# segundo_piso.net
KiCad netlist of a schematic drawn in EAGLE
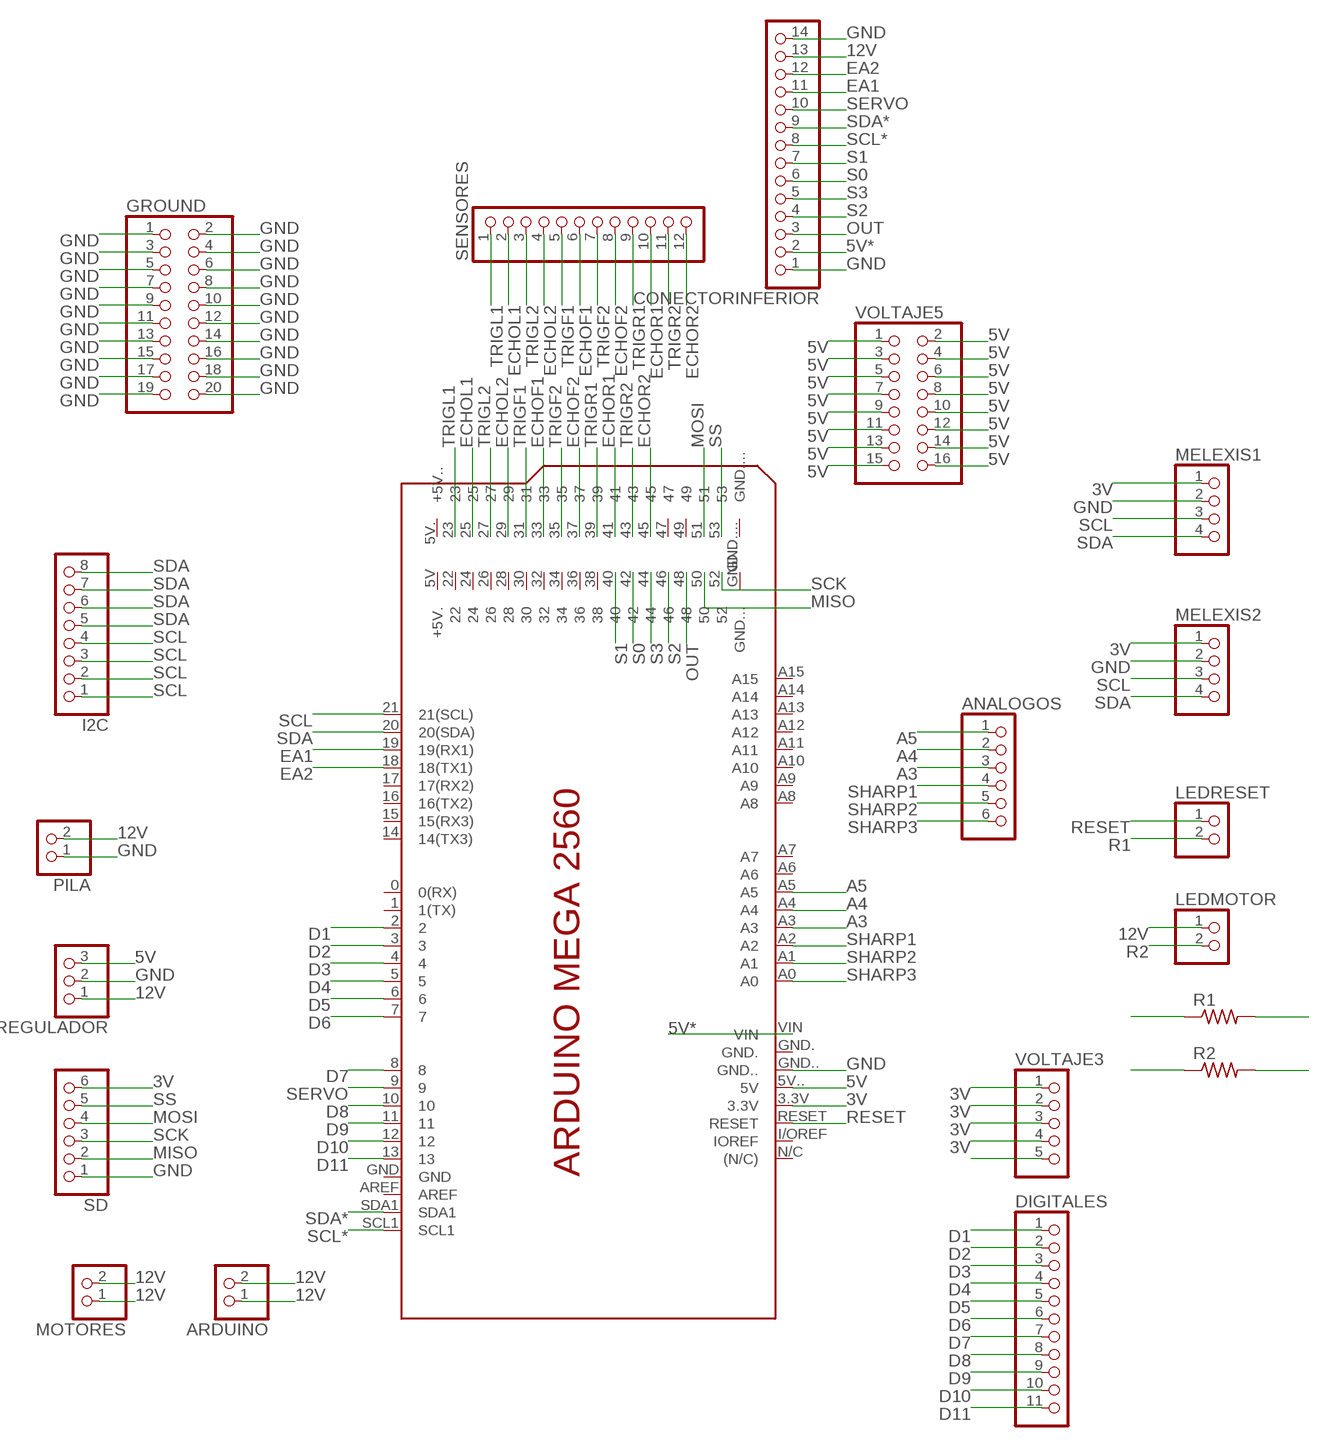
[diagram p0: schematic, sheet 1]

(export (version "E")
  (design (tool "Eeschema 10.0.6"))
  (components
    (comp (ref "ANALOGOS")
      (value "PINHD-1X6")
      (footprint "eagle-import:1X06")
      (libsource (lib "eagle-import") (part "PINHD-1X6"))
    )
    (comp (ref "ARDUINO")
      (value "PINHD-1X2")
      (footprint "eagle-import:1X02")
      (libsource (lib "eagle-import") (part "PINHD-1X2"))
    )
    (comp (ref "CONECTORINFERIOR")
      (value "PINHD-1X14")
      (footprint "eagle-import:1X14")
      (libsource (lib "eagle-import") (part "PINHD-1X14"))
    )
    (comp (ref "DIGITALES")
      (value "PINHD-1X11")
      (footprint "eagle-import:1X11")
      (libsource (lib "eagle-import") (part "PINHD-1X11"))
    )
    (comp (ref "GROUND")
      (value "PINHD-2X10")
      (footprint "eagle-import:2X10")
      (libsource (lib "eagle-import") (part "PINHD-2X10"))
    )
    (comp (ref "I2C")
      (value "PINHD-1X8")
      (footprint "eagle-import:1X08")
      (libsource (lib "eagle-import") (part "PINHD-1X8"))
    )
    (comp (ref "LEDMOTOR")
      (value "PINHD-1X2")
      (footprint "eagle-import:1X02")
      (libsource (lib "eagle-import") (part "PINHD-1X2"))
    )
    (comp (ref "LEDRESET")
      (value "PINHD-1X2")
      (footprint "eagle-import:1X02")
      (libsource (lib "eagle-import") (part "PINHD-1X2"))
    )
    (comp (ref "MEGA1")
      (value "MEGA")
      (footprint "eagle-import:MEGA")
      (libsource (lib "eagle-import") (part "MEGA"))
    )
    (comp (ref "MELEXIS1")
      (value "PINHD-1X4")
      (footprint "eagle-import:1X04")
      (libsource (lib "eagle-import") (part "PINHD-1X4"))
    )
    (comp (ref "MELEXIS2")
      (value "PINHD-1X4")
      (footprint "eagle-import:1X04")
      (libsource (lib "eagle-import") (part "PINHD-1X4"))
    )
    (comp (ref "MOTORES")
      (value "PINHD-1X2")
      (footprint "eagle-import:1X02")
      (libsource (lib "eagle-import") (part "PINHD-1X2"))
    )
    (comp (ref "PILA")
      (value "PINHD-1X2")
      (footprint "eagle-import:1X02")
      (libsource (lib "eagle-import") (part "PINHD-1X2"))
    )
    (comp (ref "R1")
      (value "R-US_0204/7")
      (footprint "eagle-import:0204_7")
      (libsource (lib "eagle-import") (part "R-US_0204/7"))
    )
    (comp (ref "R2")
      (value "R-US_0204/7")
      (footprint "eagle-import:0204_7")
      (libsource (lib "eagle-import") (part "R-US_0204/7"))
    )
    (comp (ref "REGULADOR")
      (value "PINHD-1X3")
      (footprint "eagle-import:1X03")
      (libsource (lib "eagle-import") (part "PINHD-1X3"))
    )
    (comp (ref "SD")
      (value "PINHD-1X6")
      (footprint "eagle-import:1X06")
      (libsource (lib "eagle-import") (part "PINHD-1X6"))
    )
    (comp (ref "SENSORES")
      (value "PINHD-1X12")
      (footprint "eagle-import:1X12")
      (libsource (lib "eagle-import") (part "PINHD-1X12"))
    )
    (comp (ref "VOLTAJE3")
      (value "PINHD-1X5")
      (footprint "eagle-import:1X05")
      (libsource (lib "eagle-import") (part "PINHD-1X5"))
    )
    (comp (ref "VOLTAJE5")
      (value "PINHD-2X8")
      (footprint "eagle-import:2X08")
      (libsource (lib "eagle-import") (part "PINHD-2X8"))
    )
  )
  (nets
    (net (code "1") (name "/3V") (class "Default")
      (node (ref "MEGA1") (pin "3.3V") (pinfunction "3.3V_3.3V") (pintype "bidirectional"))
      (node (ref "MELEXIS1") (pin "1") (pinfunction "1_1") (pintype "passive"))
      (node (ref "MELEXIS2") (pin "1") (pinfunction "1_1") (pintype "passive"))
      (node (ref "SD") (pin "6") (pinfunction "6_6") (pintype "passive"))
      (node (ref "VOLTAJE3") (pin "1") (pinfunction "1_1") (pintype "passive"))
      (node (ref "VOLTAJE3") (pin "2") (pinfunction "2_2") (pintype "passive"))
      (node (ref "VOLTAJE3") (pin "3") (pinfunction "3_3") (pintype "passive"))
      (node (ref "VOLTAJE3") (pin "4") (pinfunction "4_4") (pintype "passive"))
    )
    (net (code "2") (name "/5V") (class "Default")
      (node (ref "MEGA1") (pin "5V..") (pinfunction "5V_5V..") (pintype "bidirectional"))
      (node (ref "REGULADOR") (pin "3") (pinfunction "3_3") (pintype "passive"))
      (node (ref "VOLTAJE5") (pin "1") (pinfunction "1_1") (pintype "passive"))
      (node (ref "VOLTAJE5") (pin "10") (pinfunction "10_10") (pintype "passive"))
      (node (ref "VOLTAJE5") (pin "11") (pinfunction "11_11") (pintype "passive"))
      (node (ref "VOLTAJE5") (pin "12") (pinfunction "12_12") (pintype "passive"))
      (node (ref "VOLTAJE5") (pin "13") (pinfunction "13_13") (pintype "passive"))
      (node (ref "VOLTAJE5") (pin "14") (pinfunction "14_14") (pintype "passive"))
      (node (ref "VOLTAJE5") (pin "15") (pinfunction "15_15") (pintype "passive"))
      (node (ref "VOLTAJE5") (pin "16") (pinfunction "16_16") (pintype "passive"))
      (node (ref "VOLTAJE5") (pin "2") (pinfunction "2_2") (pintype "passive"))
      (node (ref "VOLTAJE5") (pin "3") (pinfunction "3_3") (pintype "passive"))
      (node (ref "VOLTAJE5") (pin "4") (pinfunction "4_4") (pintype "passive"))
      (node (ref "VOLTAJE5") (pin "5") (pinfunction "5_5") (pintype "passive"))
      (node (ref "VOLTAJE5") (pin "6") (pinfunction "6_6") (pintype "passive"))
      (node (ref "VOLTAJE5") (pin "7") (pinfunction "7_7") (pintype "passive"))
      (node (ref "VOLTAJE5") (pin "8") (pinfunction "8_8") (pintype "passive"))
      (node (ref "VOLTAJE5") (pin "9") (pinfunction "9_9") (pintype "passive"))
    )
    (net (code "3") (name "/5V*") (class "Default")
      (node (ref "CONECTORINFERIOR") (pin "2") (pinfunction "2_2") (pintype "passive"))
      (node (ref "MEGA1") (pin "VIN") (pinfunction "VIN_VIN") (pintype "bidirectional"))
    )
    (net (code "4") (name "/12V") (class "Default")
      (node (ref "ARDUINO") (pin "1") (pinfunction "1_1") (pintype "passive"))
      (node (ref "ARDUINO") (pin "2") (pinfunction "2_2") (pintype "passive"))
      (node (ref "CONECTORINFERIOR") (pin "13") (pinfunction "13_13") (pintype "passive"))
      (node (ref "LEDMOTOR") (pin "1") (pinfunction "1_1") (pintype "passive"))
      (node (ref "MOTORES") (pin "1") (pinfunction "1_1") (pintype "passive"))
      (node (ref "MOTORES") (pin "2") (pinfunction "2_2") (pintype "passive"))
      (node (ref "PILA") (pin "2") (pinfunction "2_2") (pintype "passive"))
      (node (ref "REGULADOR") (pin "1") (pinfunction "1_1") (pintype "passive"))
    )
    (net (code "5") (name "/A3") (class "Default")
      (node (ref "ANALOGOS") (pin "3") (pinfunction "3_3") (pintype "passive"))
      (node (ref "MEGA1") (pin "A3") (pinfunction "A3_A3") (pintype "bidirectional"))
    )
    (net (code "6") (name "/A4") (class "Default")
      (node (ref "ANALOGOS") (pin "2") (pinfunction "2_2") (pintype "passive"))
      (node (ref "MEGA1") (pin "A4") (pinfunction "A4_A4") (pintype "bidirectional"))
    )
    (net (code "7") (name "/A5") (class "Default")
      (node (ref "ANALOGOS") (pin "1") (pinfunction "1_1") (pintype "passive"))
      (node (ref "MEGA1") (pin "A5") (pinfunction "A5_A5") (pintype "bidirectional"))
    )
    (net (code "8") (name "/D1") (class "Default")
      (node (ref "DIGITALES") (pin "1") (pinfunction "1_1") (pintype "passive"))
      (node (ref "MEGA1") (pin "2") (pinfunction "2_2") (pintype "bidirectional"))
    )
    (net (code "9") (name "/D2") (class "Default")
      (node (ref "DIGITALES") (pin "2") (pinfunction "2_2") (pintype "passive"))
      (node (ref "MEGA1") (pin "3") (pinfunction "3_3") (pintype "bidirectional"))
    )
    (net (code "10") (name "/D3") (class "Default")
      (node (ref "DIGITALES") (pin "3") (pinfunction "3_3") (pintype "passive"))
      (node (ref "MEGA1") (pin "4") (pinfunction "4_4") (pintype "bidirectional"))
    )
    (net (code "11") (name "/D4") (class "Default")
      (node (ref "DIGITALES") (pin "4") (pinfunction "4_4") (pintype "passive"))
      (node (ref "MEGA1") (pin "5") (pinfunction "5_5") (pintype "bidirectional"))
    )
    (net (code "12") (name "/D5") (class "Default")
      (node (ref "DIGITALES") (pin "5") (pinfunction "5_5") (pintype "passive"))
      (node (ref "MEGA1") (pin "6") (pinfunction "6_6") (pintype "bidirectional"))
    )
    (net (code "13") (name "/D6") (class "Default")
      (node (ref "DIGITALES") (pin "6") (pinfunction "6_6") (pintype "passive"))
      (node (ref "MEGA1") (pin "7") (pinfunction "7_7") (pintype "bidirectional"))
    )
    (net (code "14") (name "/D7") (class "Default")
      (node (ref "DIGITALES") (pin "7") (pinfunction "7_7") (pintype "passive"))
      (node (ref "MEGA1") (pin "8") (pinfunction "8_8") (pintype "bidirectional"))
    )
    (net (code "15") (name "/D8") (class "Default")
      (node (ref "DIGITALES") (pin "8") (pinfunction "8_8") (pintype "passive"))
      (node (ref "MEGA1") (pin "10") (pinfunction "10_10") (pintype "bidirectional"))
    )
    (net (code "16") (name "/D9") (class "Default")
      (node (ref "DIGITALES") (pin "9") (pinfunction "9_9") (pintype "passive"))
      (node (ref "MEGA1") (pin "11") (pinfunction "11_11") (pintype "bidirectional"))
    )
    (net (code "17") (name "/D10") (class "Default")
      (node (ref "DIGITALES") (pin "10") (pinfunction "10_10") (pintype "passive"))
      (node (ref "MEGA1") (pin "12") (pinfunction "12_12") (pintype "bidirectional"))
    )
    (net (code "18") (name "/D11") (class "Default")
      (node (ref "DIGITALES") (pin "11") (pinfunction "11_11") (pintype "passive"))
      (node (ref "MEGA1") (pin "13") (pinfunction "13_13") (pintype "bidirectional"))
    )
    (net (code "19") (name "/EA1") (class "Default")
      (node (ref "CONECTORINFERIOR") (pin "11") (pinfunction "11_11") (pintype "passive"))
      (node (ref "MEGA1") (pin "19") (pinfunction "19(RX1)_19") (pintype "bidirectional"))
    )
    (net (code "20") (name "/EA2") (class "Default")
      (node (ref "CONECTORINFERIOR") (pin "12") (pinfunction "12_12") (pintype "passive"))
      (node (ref "MEGA1") (pin "18") (pinfunction "18(TX1)_18") (pintype "bidirectional"))
    )
    (net (code "21") (name "/ECHOF1") (class "Default")
      (node (ref "MEGA1") (pin "33") (pinfunction "33_33") (pintype "bidirectional"))
      (node (ref "SENSORES") (pin "6") (pinfunction "6_6") (pintype "passive"))
    )
    (net (code "22") (name "/ECHOF2") (class "Default")
      (node (ref "MEGA1") (pin "37") (pinfunction "37_37") (pintype "bidirectional"))
      (node (ref "SENSORES") (pin "8") (pinfunction "8_8") (pintype "passive"))
    )
    (net (code "23") (name "/ECHOL1") (class "Default")
      (node (ref "MEGA1") (pin "25") (pinfunction "25_25") (pintype "bidirectional"))
      (node (ref "SENSORES") (pin "2") (pinfunction "2_2") (pintype "passive"))
    )
    (net (code "24") (name "/ECHOL2") (class "Default")
      (node (ref "MEGA1") (pin "29") (pinfunction "29_29") (pintype "bidirectional"))
      (node (ref "SENSORES") (pin "4") (pinfunction "4_4") (pintype "passive"))
    )
    (net (code "25") (name "/ECHOR1") (class "Default")
      (node (ref "MEGA1") (pin "41") (pinfunction "41_41") (pintype "bidirectional"))
      (node (ref "SENSORES") (pin "10") (pinfunction "10_10") (pintype "passive"))
    )
    (net (code "26") (name "/ECHOR2") (class "Default")
      (node (ref "MEGA1") (pin "45") (pinfunction "45_45") (pintype "bidirectional"))
      (node (ref "SENSORES") (pin "12") (pinfunction "12_12") (pintype "passive"))
    )
    (net (code "27") (name "/GND") (class "Default")
      (node (ref "CONECTORINFERIOR") (pin "1") (pinfunction "1_1") (pintype "passive"))
      (node (ref "CONECTORINFERIOR") (pin "14") (pinfunction "14_14") (pintype "passive"))
      (node (ref "GROUND") (pin "1") (pinfunction "1_1") (pintype "passive"))
      (node (ref "GROUND") (pin "10") (pinfunction "10_10") (pintype "passive"))
      (node (ref "GROUND") (pin "11") (pinfunction "11_11") (pintype "passive"))
      (node (ref "GROUND") (pin "12") (pinfunction "12_12") (pintype "passive"))
      (node (ref "GROUND") (pin "13") (pinfunction "13_13") (pintype "passive"))
      (node (ref "GROUND") (pin "14") (pinfunction "14_14") (pintype "passive"))
      (node (ref "GROUND") (pin "15") (pinfunction "15_15") (pintype "passive"))
      (node (ref "GROUND") (pin "16") (pinfunction "16_16") (pintype "passive"))
      (node (ref "GROUND") (pin "17") (pinfunction "17_17") (pintype "passive"))
      (node (ref "GROUND") (pin "18") (pinfunction "18_18") (pintype "passive"))
      (node (ref "GROUND") (pin "19") (pinfunction "19_19") (pintype "passive"))
      (node (ref "GROUND") (pin "2") (pinfunction "2_2") (pintype "passive"))
      (node (ref "GROUND") (pin "20") (pinfunction "20_20") (pintype "passive"))
      (node (ref "GROUND") (pin "3") (pinfunction "3_3") (pintype "passive"))
      (node (ref "GROUND") (pin "4") (pinfunction "4_4") (pintype "passive"))
      (node (ref "GROUND") (pin "5") (pinfunction "5_5") (pintype "passive"))
      (node (ref "GROUND") (pin "6") (pinfunction "6_6") (pintype "passive"))
      (node (ref "GROUND") (pin "7") (pinfunction "7_7") (pintype "passive"))
      (node (ref "GROUND") (pin "8") (pinfunction "8_8") (pintype "passive"))
      (node (ref "GROUND") (pin "9") (pinfunction "9_9") (pintype "passive"))
      (node (ref "MEGA1") (pin "GND..") (pinfunction "GND.._GND..") (pintype "bidirectional"))
      (node (ref "MELEXIS1") (pin "2") (pinfunction "2_2") (pintype "passive"))
      (node (ref "MELEXIS2") (pin "2") (pinfunction "2_2") (pintype "passive"))
      (node (ref "PILA") (pin "1") (pinfunction "1_1") (pintype "passive"))
      (node (ref "R1") (pin "2") (pinfunction "2_2") (pintype "passive"))
      (node (ref "R2") (pin "2") (pinfunction "2_2") (pintype "passive"))
      (node (ref "REGULADOR") (pin "2") (pinfunction "2_2") (pintype "passive"))
      (node (ref "SD") (pin "1") (pinfunction "1_1") (pintype "passive"))
    )
    (net (code "28") (name "/MISO") (class "Default")
      (node (ref "MEGA1") (pin "50") (pinfunction "50_50") (pintype "bidirectional"))
      (node (ref "SD") (pin "2") (pinfunction "2_2") (pintype "passive"))
    )
    (net (code "29") (name "/MOSI") (class "Default")
      (node (ref "MEGA1") (pin "51") (pinfunction "51_51") (pintype "bidirectional"))
      (node (ref "SD") (pin "4") (pinfunction "4_4") (pintype "passive"))
    )
    (net (code "30") (name "/OUT") (class "Default")
      (node (ref "CONECTORINFERIOR") (pin "3") (pinfunction "3_3") (pintype "passive"))
      (node (ref "MEGA1") (pin "48") (pinfunction "48_48") (pintype "bidirectional"))
    )
    (net (code "31") (name "/R1") (class "Default")
      (node (ref "LEDRESET") (pin "2") (pinfunction "2_2") (pintype "passive"))
      (node (ref "R1") (pin "1") (pinfunction "1_1") (pintype "passive"))
    )
    (net (code "32") (name "/R2") (class "Default")
      (node (ref "LEDMOTOR") (pin "2") (pinfunction "2_2") (pintype "passive"))
      (node (ref "R2") (pin "1") (pinfunction "1_1") (pintype "passive"))
    )
    (net (code "33") (name "/RESET") (class "Default")
      (node (ref "LEDRESET") (pin "1") (pinfunction "1_1") (pintype "passive"))
      (node (ref "MEGA1") (pin "RESET") (pinfunction "RESET_RESET") (pintype "bidirectional"))
      (node (ref "VOLTAJE3") (pin "5") (pinfunction "5_5") (pintype "passive"))
    )
    (net (code "34") (name "/S0") (class "Default")
      (node (ref "CONECTORINFERIOR") (pin "6") (pinfunction "6_6") (pintype "passive"))
      (node (ref "MEGA1") (pin "42") (pinfunction "42_42") (pintype "bidirectional"))
    )
    (net (code "35") (name "/S1") (class "Default")
      (node (ref "CONECTORINFERIOR") (pin "7") (pinfunction "7_7") (pintype "passive"))
      (node (ref "MEGA1") (pin "40") (pinfunction "40_40") (pintype "bidirectional"))
    )
    (net (code "36") (name "/S2") (class "Default")
      (node (ref "CONECTORINFERIOR") (pin "4") (pinfunction "4_4") (pintype "passive"))
      (node (ref "MEGA1") (pin "46") (pinfunction "46_46") (pintype "bidirectional"))
    )
    (net (code "37") (name "/S3") (class "Default")
      (node (ref "CONECTORINFERIOR") (pin "5") (pinfunction "5_5") (pintype "passive"))
      (node (ref "MEGA1") (pin "44") (pinfunction "44_44") (pintype "bidirectional"))
    )
    (net (code "38") (name "/SCK") (class "Default")
      (node (ref "MEGA1") (pin "52") (pinfunction "52_52") (pintype "bidirectional"))
      (node (ref "SD") (pin "3") (pinfunction "3_3") (pintype "passive"))
    )
    (net (code "39") (name "/SCL") (class "Default")
      (node (ref "I2C") (pin "1") (pinfunction "1_1") (pintype "passive"))
      (node (ref "I2C") (pin "2") (pinfunction "2_2") (pintype "passive"))
      (node (ref "I2C") (pin "3") (pinfunction "3_3") (pintype "passive"))
      (node (ref "I2C") (pin "4") (pinfunction "4_4") (pintype "passive"))
      (node (ref "MEGA1") (pin "21") (pinfunction "21(SCL)_21") (pintype "bidirectional"))
      (node (ref "MELEXIS1") (pin "3") (pinfunction "3_3") (pintype "passive"))
      (node (ref "MELEXIS2") (pin "3") (pinfunction "3_3") (pintype "passive"))
    )
    (net (code "40") (name "/SCL*") (class "Default")
      (node (ref "CONECTORINFERIOR") (pin "8") (pinfunction "8_8") (pintype "passive"))
      (node (ref "MEGA1") (pin "SCL1") (pinfunction "SCL1_SCL1") (pintype "bidirectional"))
    )
    (net (code "41") (name "/SDA") (class "Default")
      (node (ref "I2C") (pin "5") (pinfunction "5_5") (pintype "passive"))
      (node (ref "I2C") (pin "6") (pinfunction "6_6") (pintype "passive"))
      (node (ref "I2C") (pin "7") (pinfunction "7_7") (pintype "passive"))
      (node (ref "I2C") (pin "8") (pinfunction "8_8") (pintype "passive"))
      (node (ref "MEGA1") (pin "20") (pinfunction "20(SDA)_20") (pintype "bidirectional"))
      (node (ref "MELEXIS1") (pin "4") (pinfunction "4_4") (pintype "passive"))
      (node (ref "MELEXIS2") (pin "4") (pinfunction "4_4") (pintype "passive"))
    )
    (net (code "42") (name "/SDA*") (class "Default")
      (node (ref "CONECTORINFERIOR") (pin "9") (pinfunction "9_9") (pintype "passive"))
      (node (ref "MEGA1") (pin "SDA1") (pinfunction "SDA1_SDA1") (pintype "bidirectional"))
    )
    (net (code "43") (name "/SERVO") (class "Default")
      (node (ref "CONECTORINFERIOR") (pin "10") (pinfunction "10_10") (pintype "passive"))
      (node (ref "MEGA1") (pin "9") (pinfunction "9_9") (pintype "bidirectional"))
    )
    (net (code "44") (name "/SHARP1") (class "Default")
      (node (ref "ANALOGOS") (pin "4") (pinfunction "4_4") (pintype "passive"))
      (node (ref "MEGA1") (pin "A2") (pinfunction "A2_A2") (pintype "bidirectional"))
    )
    (net (code "45") (name "/SHARP2") (class "Default")
      (node (ref "ANALOGOS") (pin "5") (pinfunction "5_5") (pintype "passive"))
      (node (ref "MEGA1") (pin "A1") (pinfunction "A1_A1") (pintype "bidirectional"))
    )
    (net (code "46") (name "/SHARP3") (class "Default")
      (node (ref "ANALOGOS") (pin "6") (pinfunction "6_6") (pintype "passive"))
      (node (ref "MEGA1") (pin "A0") (pinfunction "A0_A0") (pintype "bidirectional"))
    )
    (net (code "47") (name "/SS") (class "Default")
      (node (ref "MEGA1") (pin "53") (pinfunction "53_53") (pintype "bidirectional"))
      (node (ref "SD") (pin "5") (pinfunction "5_5") (pintype "passive"))
    )
    (net (code "48") (name "/TRIGF1") (class "Default")
      (node (ref "MEGA1") (pin "31") (pinfunction "31_31") (pintype "bidirectional"))
      (node (ref "SENSORES") (pin "5") (pinfunction "5_5") (pintype "passive"))
    )
    (net (code "49") (name "/TRIGF2") (class "Default")
      (node (ref "MEGA1") (pin "35") (pinfunction "35_35") (pintype "bidirectional"))
      (node (ref "SENSORES") (pin "7") (pinfunction "7_7") (pintype "passive"))
    )
    (net (code "50") (name "/TRIGL1") (class "Default")
      (node (ref "MEGA1") (pin "23") (pinfunction "23_23") (pintype "bidirectional"))
      (node (ref "SENSORES") (pin "1") (pinfunction "1_1") (pintype "passive"))
    )
    (net (code "51") (name "/TRIGL2") (class "Default")
      (node (ref "MEGA1") (pin "27") (pinfunction "27_27") (pintype "bidirectional"))
      (node (ref "SENSORES") (pin "3") (pinfunction "3_3") (pintype "passive"))
    )
    (net (code "52") (name "/TRIGR1") (class "Default")
      (node (ref "MEGA1") (pin "39") (pinfunction "39_39") (pintype "bidirectional"))
      (node (ref "SENSORES") (pin "9") (pinfunction "9_9") (pintype "passive"))
    )
    (net (code "53") (name "/TRIGR2") (class "Default")
      (node (ref "MEGA1") (pin "43") (pinfunction "43_43") (pintype "bidirectional"))
      (node (ref "SENSORES") (pin "11") (pinfunction "11_11") (pintype "passive"))
    )
    (net (code "54") (name "unconnected-(MEGA1-(N{slash}C)-PadN{slash}C)") (class "Default")
      (node (ref "MEGA1") (pin "N/C") (pinfunction "(N/C)_N/C") (pintype "bidirectional"))
    )
    (net (code "55") (name "unconnected-(MEGA1-+5V.-Pad5V)") (class "Default")
      (node (ref "MEGA1") (pin "5V") (pinfunction "+5V._5V") (pintype "bidirectional"))
    )
    (net (code "56") (name "unconnected-(MEGA1-+5V..-Pad5V.)") (class "Default")
      (node (ref "MEGA1") (pin "5V.") (pinfunction "+5V.._5V.") (pintype "bidirectional"))
    )
    (net (code "57") (name "unconnected-(MEGA1-0(RX)-Pad0)") (class "Default")
      (node (ref "MEGA1") (pin "0") (pinfunction "0(RX)_0") (pintype "bidirectional"))
    )
    (net (code "58") (name "unconnected-(MEGA1-1(TX)-Pad1)") (class "Default")
      (node (ref "MEGA1") (pin "1") (pinfunction "1(TX)_1") (pintype "bidirectional"))
    )
    (net (code "59") (name "unconnected-(MEGA1-14(TX3)-Pad14)") (class "Default")
      (node (ref "MEGA1") (pin "14") (pinfunction "14(TX3)_14") (pintype "bidirectional"))
    )
    (net (code "60") (name "unconnected-(MEGA1-15(RX3)-Pad15)") (class "Default")
      (node (ref "MEGA1") (pin "15") (pinfunction "15(RX3)_15") (pintype "bidirectional"))
    )
    (net (code "61") (name "unconnected-(MEGA1-16(TX2)-Pad16)") (class "Default")
      (node (ref "MEGA1") (pin "16") (pinfunction "16(TX2)_16") (pintype "bidirectional"))
    )
    (net (code "62") (name "unconnected-(MEGA1-17(RX2)-Pad17)") (class "Default")
      (node (ref "MEGA1") (pin "17") (pinfunction "17(RX2)_17") (pintype "bidirectional"))
    )
    (net (code "63") (name "unconnected-(MEGA1-IOREF-PadI{slash}OREF)") (class "Default")
      (node (ref "MEGA1") (pin "I/OREF") (pinfunction "IOREF_I/OREF") (pintype "bidirectional"))
    )
    (net (code "64") (name "unconnected-(MEGA1-Pad22)") (class "Default")
      (node (ref "MEGA1") (pin "22") (pinfunction "22_22") (pintype "bidirectional"))
    )
    (net (code "65") (name "unconnected-(MEGA1-Pad24)") (class "Default")
      (node (ref "MEGA1") (pin "24") (pinfunction "24_24") (pintype "bidirectional"))
    )
    (net (code "66") (name "unconnected-(MEGA1-Pad26)") (class "Default")
      (node (ref "MEGA1") (pin "26") (pinfunction "26_26") (pintype "bidirectional"))
    )
    (net (code "67") (name "unconnected-(MEGA1-Pad28)") (class "Default")
      (node (ref "MEGA1") (pin "28") (pinfunction "28_28") (pintype "bidirectional"))
    )
    (net (code "68") (name "unconnected-(MEGA1-Pad30)") (class "Default")
      (node (ref "MEGA1") (pin "30") (pinfunction "30_30") (pintype "bidirectional"))
    )
    (net (code "69") (name "unconnected-(MEGA1-Pad32)") (class "Default")
      (node (ref "MEGA1") (pin "32") (pinfunction "32_32") (pintype "bidirectional"))
    )
    (net (code "70") (name "unconnected-(MEGA1-Pad34)") (class "Default")
      (node (ref "MEGA1") (pin "34") (pinfunction "34_34") (pintype "bidirectional"))
    )
    (net (code "71") (name "unconnected-(MEGA1-Pad36)") (class "Default")
      (node (ref "MEGA1") (pin "36") (pinfunction "36_36") (pintype "bidirectional"))
    )
    (net (code "72") (name "unconnected-(MEGA1-Pad38)") (class "Default")
      (node (ref "MEGA1") (pin "38") (pinfunction "38_38") (pintype "bidirectional"))
    )
    (net (code "73") (name "unconnected-(MEGA1-Pad47)") (class "Default")
      (node (ref "MEGA1") (pin "47") (pinfunction "47_47") (pintype "bidirectional"))
    )
    (net (code "74") (name "unconnected-(MEGA1-Pad49)") (class "Default")
      (node (ref "MEGA1") (pin "49") (pinfunction "49_49") (pintype "bidirectional"))
    )
    (net (code "75") (name "unconnected-(MEGA1-PadA6)") (class "Default")
      (node (ref "MEGA1") (pin "A6") (pinfunction "A6_A6") (pintype "bidirectional"))
    )
    (net (code "76") (name "unconnected-(MEGA1-PadA7)") (class "Default")
      (node (ref "MEGA1") (pin "A7") (pinfunction "A7_A7") (pintype "bidirectional"))
    )
    (net (code "77") (name "unconnected-(MEGA1-PadA8)") (class "Default")
      (node (ref "MEGA1") (pin "A8") (pinfunction "A8_A8") (pintype "bidirectional"))
    )
    (net (code "78") (name "unconnected-(MEGA1-PadA9)") (class "Default")
      (node (ref "MEGA1") (pin "A9") (pinfunction "A9_A9") (pintype "bidirectional"))
    )
    (net (code "79") (name "unconnected-(MEGA1-PadA10)") (class "Default")
      (node (ref "MEGA1") (pin "A10") (pinfunction "A10_A10") (pintype "bidirectional"))
    )
    (net (code "80") (name "unconnected-(MEGA1-PadA11)") (class "Default")
      (node (ref "MEGA1") (pin "A11") (pinfunction "A11_A11") (pintype "bidirectional"))
    )
    (net (code "81") (name "unconnected-(MEGA1-PadA12)") (class "Default")
      (node (ref "MEGA1") (pin "A12") (pinfunction "A12_A12") (pintype "bidirectional"))
    )
    (net (code "82") (name "unconnected-(MEGA1-PadA13)") (class "Default")
      (node (ref "MEGA1") (pin "A13") (pinfunction "A13_A13") (pintype "bidirectional"))
    )
    (net (code "83") (name "unconnected-(MEGA1-PadA14)") (class "Default")
      (node (ref "MEGA1") (pin "A14") (pinfunction "A14_A14") (pintype "bidirectional"))
    )
    (net (code "84") (name "unconnected-(MEGA1-PadA15)") (class "Default")
      (node (ref "MEGA1") (pin "A15") (pinfunction "A15_A15") (pintype "bidirectional"))
    )
    (net (code "85") (name "unconnected-(MEGA1-PadAREF)") (class "Default")
      (node (ref "MEGA1") (pin "AREF") (pinfunction "AREF_AREF") (pintype "bidirectional"))
    )
    (net (code "86") (name "unconnected-(MEGA1-PadGND)") (class "Default")
      (node (ref "MEGA1") (pin "GND") (pinfunction "GND_GND") (pintype "bidirectional"))
    )
    (net (code "87") (name "unconnected-(MEGA1-PadGND.)") (class "Default")
      (node (ref "MEGA1") (pin "GND.") (pinfunction "GND._GND.") (pintype "bidirectional"))
    )
    (net (code "88") (name "unconnected-(MEGA1-PadGND...)") (class "Default")
      (node (ref "MEGA1") (pin "GND...") (pinfunction "GND..._GND...") (pintype "bidirectional"))
    )
    (net (code "89") (name "unconnected-(MEGA1-PadGND....)") (class "Default")
      (node (ref "MEGA1") (pin "GND....") (pinfunction "GND...._GND....") (pintype "bidirectional"))
    )
  )
)
